# Universal_2022_06.net
KiCad netlist of a schematic drawn in EAGLE
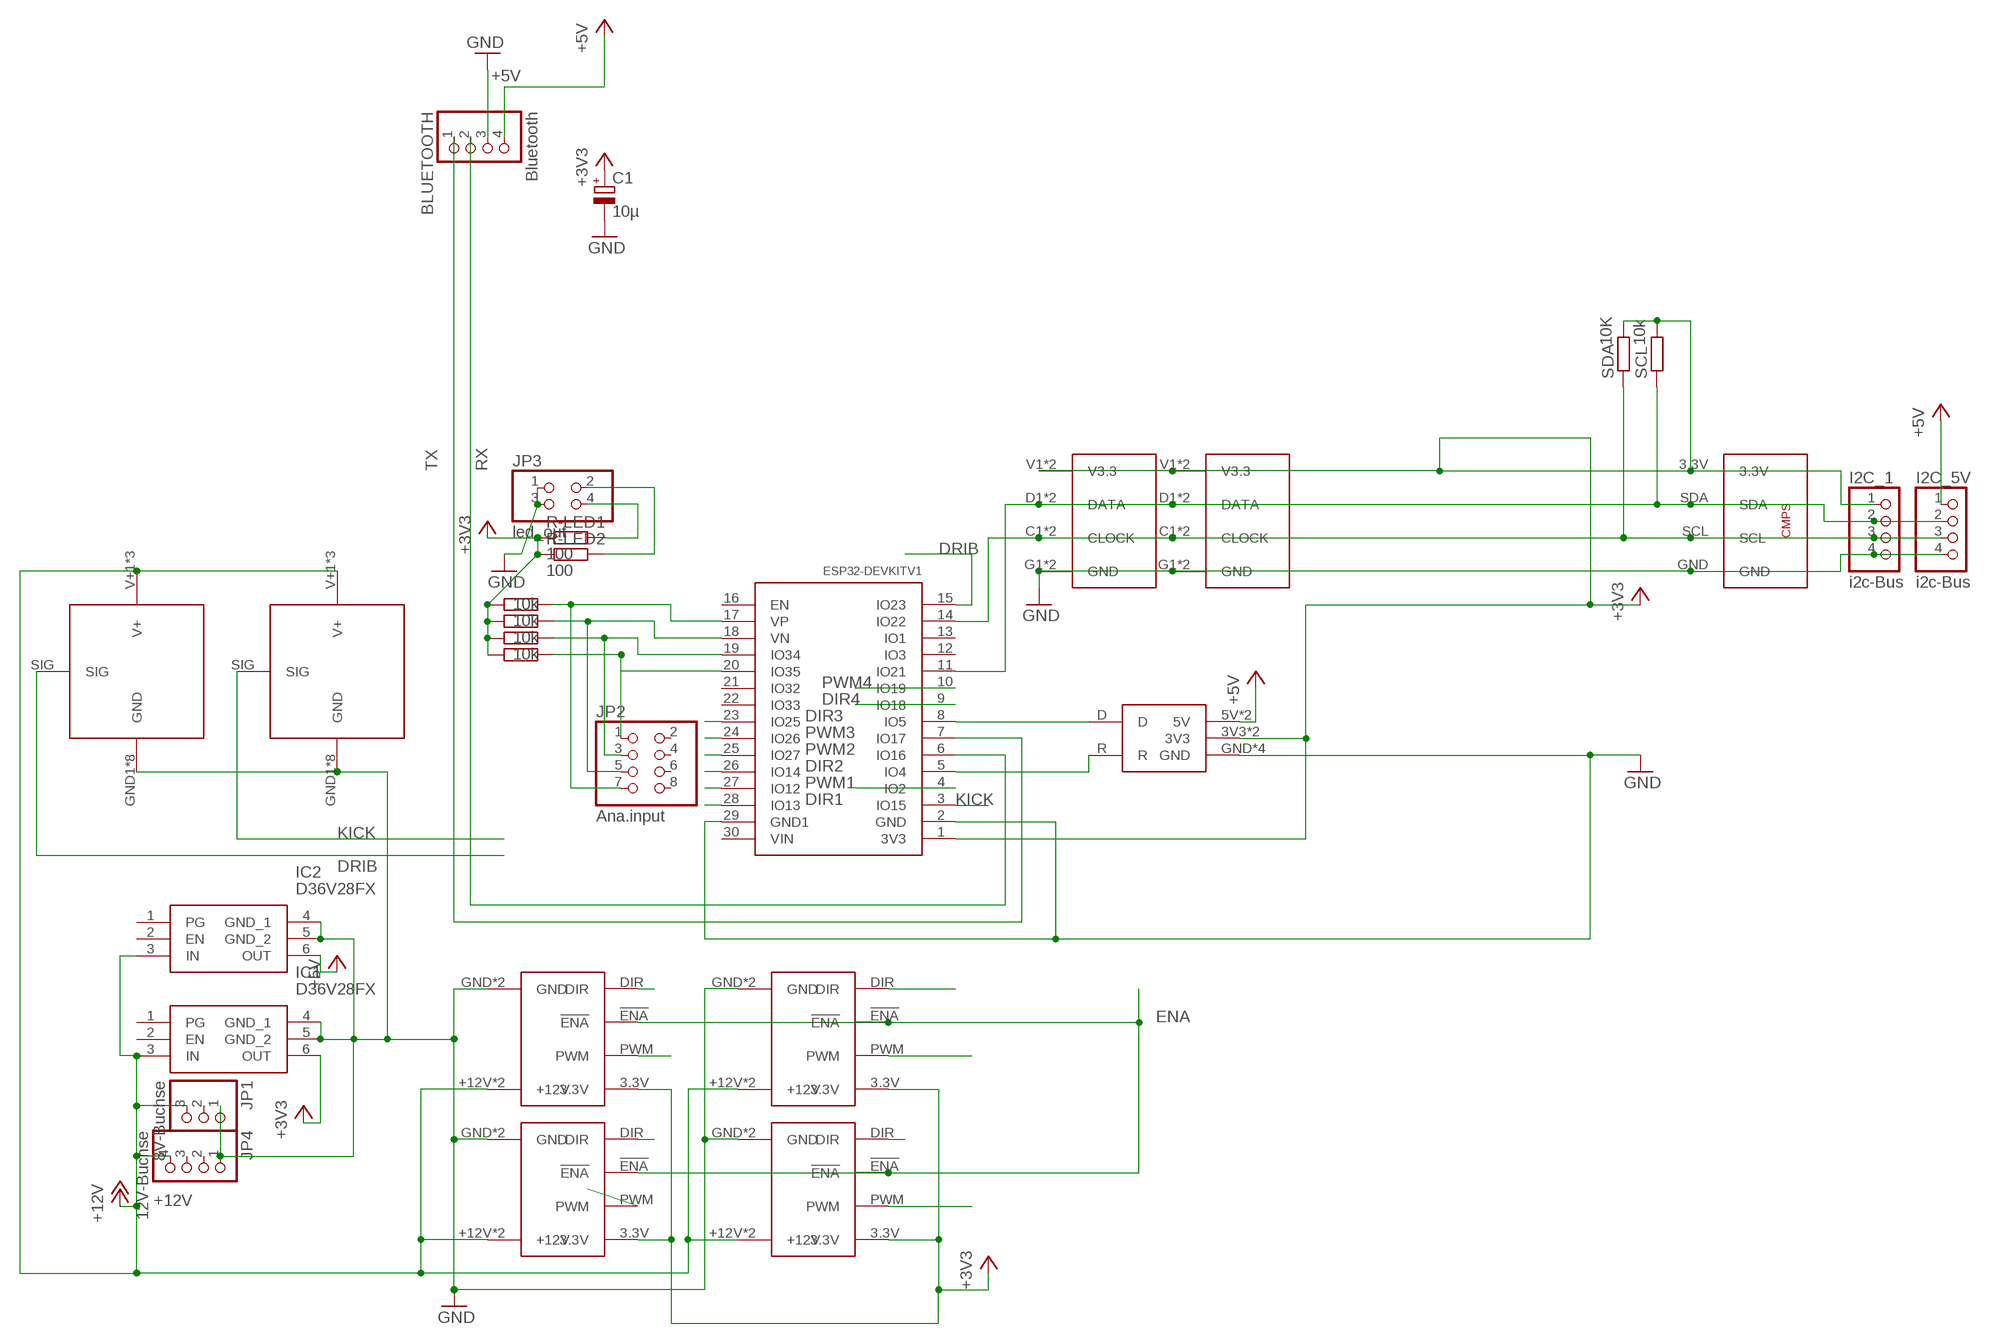
[diagram p0: schematic, sheet 1]

(export (version "E")
  (design (tool "Eeschema 10.0.6"))
  (components
    (comp (ref "BLUETOOTH")
      (value "Bluetooth")
      (footprint "eagle-import:1X04_90")
      (libsource (lib "eagle-import") (part "PINHD-1X4/90"))
    )
    (comp (ref "C1")
      (value "10µ")
      (footprint "eagle-import:E2,5-6E")
      (libsource (lib "eagle-import") (part "CPOL-EUE2,5-6E"))
    )
    (comp (ref "I2C_1")
      (value "i2c-Bus")
      (footprint "eagle-import:1X04")
      (libsource (lib "eagle-import") (part "PINHD-1X4"))
    )
    (comp (ref "I2C_5V")
      (value "i2c-Bus")
      (footprint "eagle-import:1X04")
      (libsource (lib "eagle-import") (part "PINHD-1X4"))
    )
    (comp (ref "IC1")
      (value "D36V28FX")
      (footprint "eagle-import:D36V28FX")
      (libsource (lib "eagle-import") (part "D36V28FX"))
    )
    (comp (ref "IC2")
      (value "D36V28FX")
      (footprint "eagle-import:D36V28FX")
      (libsource (lib "eagle-import") (part "D36V28FX"))
    )
    (comp (ref "JP1")
      (value "8V-Buchse")
      (footprint "eagle-import:1X03")
      (libsource (lib "eagle-import") (part "PINHD-1X3"))
    )
    (comp (ref "JP2")
      (value "Ana.input")
      (footprint "eagle-import:2X04")
      (libsource (lib "eagle-import") (part "PINHD-2X4"))
    )
    (comp (ref "JP3")
      (value "led_out")
      (footprint "eagle-import:2X02")
      (libsource (lib "eagle-import") (part "PINHD-2X2"))
    )
    (comp (ref "JP4")
      (value "12V-Buchse")
      (footprint "eagle-import:1X04")
      (libsource (lib "eagle-import") (part "PINHD-1X4"))
    )
    (comp (ref "R-LED1")
      (value "100")
      (footprint "eagle-import:0207_10")
      (libsource (lib "eagle-import") (part "R-EU_0207/10"))
    )
    (comp (ref "R-LED2")
      (value "100")
      (footprint "eagle-import:0207_10")
      (libsource (lib "eagle-import") (part "R-EU_0207/10"))
    )
    (comp (ref "R_AD14")
      (value "10k")
      (footprint "eagle-import:0207_10")
      (libsource (lib "eagle-import") (part "R-EU_0207/10"))
    )
    (comp (ref "R_AD25")
      (value "10k")
      (footprint "eagle-import:0207_10")
      (libsource (lib "eagle-import") (part "R-EU_0207/10"))
    )
    (comp (ref "R_AD26")
      (value "10k")
      (footprint "eagle-import:0207_10")
      (libsource (lib "eagle-import") (part "R-EU_0207/10"))
    )
    (comp (ref "R_AD27")
      (value "10k")
      (footprint "eagle-import:0207_10")
      (libsource (lib "eagle-import") (part "R-EU_0207/10"))
    )
    (comp (ref "SCL")
      (value "10k")
      (footprint "eagle-import:0207_10")
      (libsource (lib "eagle-import") (part "R-EU_0207/10"))
    )
    (comp (ref "SDA")
      (value "10K")
      (footprint "eagle-import:0207_10")
      (libsource (lib "eagle-import") (part "R-EU_0207/10"))
    )
    (comp (ref "U$1")
      (value "TASTER_LED")
      (footprint "eagle-import:TASTER_LED")
      (libsource (lib "eagle-import") (part "TASTER_LED"))
    )
    (comp (ref "U$3")
      (value "TASTER_LED")
      (footprint "eagle-import:TASTER_LED")
      (libsource (lib "eagle-import") (part "TASTER_LED"))
    )
    (comp (ref "U$5")
      (value "CANBUS")
      (footprint "eagle-import:CANBUS")
      (libsource (lib "eagle-import") (part "CANBUS"))
    )
    (comp (ref "U$7")
      (value "KICKER")
      (footprint "eagle-import:KICKER")
      (libsource (lib "eagle-import") (part "KICKER"))
    )
    (comp (ref "U$8")
      (value "CMPS")
      (footprint "eagle-import:CMPS")
      (libsource (lib "eagle-import") (part "CMPS"))
    )
    (comp (ref "U$11")
      (value "IFX9201BREAKOUT")
      (footprint "eagle-import:IFX9201BREAKOUT")
      (libsource (lib "eagle-import") (part "IFX9201BREAKOUT"))
    )
    (comp (ref "U$13")
      (value "ESP32DEVKITV1")
      (footprint "eagle-import:ESP32-DEVKITV1")
      (libsource (lib "eagle-import") (part "ESP32DEVKITV1"))
    )
    (comp (ref "U$14")
      (value "IFX9201BREAKOUT")
      (footprint "eagle-import:IFX9201BREAKOUT")
      (libsource (lib "eagle-import") (part "IFX9201BREAKOUT"))
    )
    (comp (ref "U$15")
      (value "IFX9201BREAKOUT")
      (footprint "eagle-import:IFX9201BREAKOUT")
      (libsource (lib "eagle-import") (part "IFX9201BREAKOUT"))
    )
    (comp (ref "U$16")
      (value "IFX9201BREAKOUT")
      (footprint "eagle-import:IFX9201BREAKOUT")
      (libsource (lib "eagle-import") (part "IFX9201BREAKOUT"))
    )
    (comp (ref "U$17")
      (value "KICKER")
      (footprint "eagle-import:KICKER")
      (libsource (lib "eagle-import") (part "KICKER"))
    )
  )
  (nets
    (net (code "1") (name "+3V3") (class "Default")
      (node (ref "C1") (pin "+") (pinfunction "+_+") (pintype "passive"))
      (node (ref "I2C_1") (pin "1") (pinfunction "1_1") (pintype "passive"))
      (node (ref "IC1") (pin "6") (pinfunction "OUT_6") (pintype "bidirectional"))
      (node (ref "R-LED1") (pin "1") (pinfunction "1_1") (pintype "passive"))
      (node (ref "R-LED2") (pin "1") (pinfunction "1_1") (pintype "passive"))
      (node (ref "R_AD14") (pin "1") (pinfunction "1_1") (pintype "passive"))
      (node (ref "R_AD25") (pin "1") (pinfunction "1_1") (pintype "passive"))
      (node (ref "R_AD26") (pin "1") (pinfunction "1_1") (pintype "passive"))
      (node (ref "R_AD27") (pin "1") (pinfunction "1_1") (pintype "passive"))
      (node (ref "SCL") (pin "2") (pinfunction "2_2") (pintype "passive"))
      (node (ref "SDA") (pin "2") (pinfunction "2_2") (pintype "passive"))
      (node (ref "U$1") (pin "V1") (pinfunction "V3.3_V1") (pintype "bidirectional"))
      (node (ref "U$1") (pin "V2") (pinfunction "V3.3_V2") (pintype "bidirectional"))
      (node (ref "U$11") (pin "3.3V") (pinfunction "3.3V_3.3V") (pintype "bidirectional"))
      (node (ref "U$13") (pin "1") (pinfunction "3V3_1") (pintype "bidirectional"))
      (node (ref "U$14") (pin "3.3V") (pinfunction "3.3V_3.3V") (pintype "bidirectional"))
      (node (ref "U$15") (pin "3.3V") (pinfunction "3.3V_3.3V") (pintype "bidirectional"))
      (node (ref "U$16") (pin "3.3V") (pinfunction "3.3V_3.3V") (pintype "bidirectional"))
      (node (ref "U$3") (pin "V1") (pinfunction "V3.3_V1") (pintype "bidirectional"))
      (node (ref "U$3") (pin "V2") (pinfunction "V3.3_V2") (pintype "bidirectional"))
      (node (ref "U$5") (pin "3V3") (pinfunction "3V3_3V3") (pintype "bidirectional"))
      (node (ref "U$5") (pin "3V3_1") (pinfunction "3V3_3V3_1") (pintype "bidirectional"))
      (node (ref "U$8") (pin "3.3V") (pinfunction "3.3V_3.3V") (pintype "bidirectional"))
    )
    (net (code "2") (name "+5V") (class "Default")
      (node (ref "BLUETOOTH") (pin "4") (pinfunction "4_4") (pintype "passive"))
      (node (ref "I2C_5V") (pin "1") (pinfunction "1_1") (pintype "passive"))
      (node (ref "IC2") (pin "6") (pinfunction "OUT_6") (pintype "bidirectional"))
      (node (ref "U$5") (pin "5V") (pinfunction "5V_5V") (pintype "bidirectional"))
      (node (ref "U$5") (pin "5V_1") (pinfunction "5V_5V_1") (pintype "bidirectional"))
    )
    (net (code "3") (name "+12V") (class "Default")
      (node (ref "IC1") (pin "3") (pinfunction "IN_3") (pintype "bidirectional"))
      (node (ref "IC2") (pin "3") (pinfunction "IN_3") (pintype "bidirectional"))
      (node (ref "JP1") (pin "3") (pinfunction "3_3") (pintype "passive"))
      (node (ref "JP4") (pin "4") (pinfunction "4_4") (pintype "passive"))
      (node (ref "U$11") (pin "+12V") (pinfunction "+12V_+12V") (pintype "bidirectional"))
      (node (ref "U$11") (pin "+12V2") (pinfunction "+12V_+12V2") (pintype "bidirectional"))
      (node (ref "U$14") (pin "+12V") (pinfunction "+12V_+12V") (pintype "bidirectional"))
      (node (ref "U$14") (pin "+12V2") (pinfunction "+12V_+12V2") (pintype "bidirectional"))
      (node (ref "U$15") (pin "+12V") (pinfunction "+12V_+12V") (pintype "bidirectional"))
      (node (ref "U$15") (pin "+12V2") (pinfunction "+12V_+12V2") (pintype "bidirectional"))
      (node (ref "U$16") (pin "+12V") (pinfunction "+12V_+12V") (pintype "bidirectional"))
      (node (ref "U$16") (pin "+12V2") (pinfunction "+12V_+12V2") (pintype "bidirectional"))
      (node (ref "U$17") (pin "V+1") (pinfunction "V+_V+1") (pintype "bidirectional"))
      (node (ref "U$17") (pin "V+2") (pinfunction "V+_V+2") (pintype "bidirectional"))
      (node (ref "U$17") (pin "V+3") (pinfunction "V+_V+3") (pintype "bidirectional"))
      (node (ref "U$7") (pin "V+1") (pinfunction "V+_V+1") (pintype "bidirectional"))
      (node (ref "U$7") (pin "V+2") (pinfunction "V+_V+2") (pintype "bidirectional"))
      (node (ref "U$7") (pin "V+3") (pinfunction "V+_V+3") (pintype "bidirectional"))
    )
    (net (code "4") (name "/DIR1") (class "Default")
      (node (ref "U$13") (pin "28") (pinfunction "IO13_28") (pintype "bidirectional"))
      (node (ref "U$16") (pin "DIR") (pinfunction "DIR_DIR") (pintype "bidirectional"))
    )
    (net (code "5") (name "/DIR2") (class "Default")
      (node (ref "U$13") (pin "26") (pinfunction "IO14_26") (pintype "bidirectional"))
      (node (ref "U$15") (pin "DIR") (pinfunction "DIR_DIR") (pintype "bidirectional"))
    )
    (net (code "6") (name "/DIR3") (class "Default")
      (node (ref "U$11") (pin "DIR") (pinfunction "DIR_DIR") (pintype "bidirectional"))
      (node (ref "U$13") (pin "23") (pinfunction "IO25_23") (pintype "bidirectional"))
    )
    (net (code "7") (name "/DIR4") (class "Default")
      (node (ref "U$13") (pin "9") (pinfunction "IO18_9") (pintype "bidirectional"))
      (node (ref "U$14") (pin "DIR") (pinfunction "DIR_DIR") (pintype "bidirectional"))
    )
    (net (code "8") (name "/DRIB") (class "Default")
      (node (ref "U$13") (pin "15") (pinfunction "IO23_15") (pintype "bidirectional"))
      (node (ref "U$7") (pin "SIG") (pinfunction "SIG_SIG") (pintype "bidirectional"))
    )
    (net (code "9") (name "/ENA") (class "Default")
      (node (ref "U$11") (pin "!ENA") (pinfunction "~{ENA}_!ENA") (pintype "bidirectional"))
      (node (ref "U$13") (pin "4") (pinfunction "IO2_4") (pintype "bidirectional"))
      (node (ref "U$14") (pin "!ENA") (pinfunction "~{ENA}_!ENA") (pintype "bidirectional"))
      (node (ref "U$15") (pin "!ENA") (pinfunction "~{ENA}_!ENA") (pintype "bidirectional"))
      (node (ref "U$16") (pin "!ENA") (pinfunction "~{ENA}_!ENA") (pintype "bidirectional"))
    )
    (net (code "10") (name "/KICK") (class "Default")
      (node (ref "U$13") (pin "3") (pinfunction "IO15_3") (pintype "bidirectional"))
      (node (ref "U$17") (pin "SIG") (pinfunction "SIG_SIG") (pintype "bidirectional"))
    )
    (net (code "11") (name "/PWM1") (class "Default")
      (node (ref "U$13") (pin "27") (pinfunction "IO12_27") (pintype "bidirectional"))
      (node (ref "U$16") (pin "PWM") (pinfunction "PWM_PWM") (pintype "bidirectional"))
    )
    (net (code "12") (name "/PWM2") (class "Default")
      (node (ref "U$13") (pin "25") (pinfunction "IO27_25") (pintype "bidirectional"))
      (node (ref "U$15") (pin "PWM") (pinfunction "PWM_PWM") (pintype "bidirectional"))
    )
    (net (code "13") (name "/PWM3") (class "Default")
      (node (ref "U$11") (pin "PWM") (pinfunction "PWM_PWM") (pintype "bidirectional"))
      (node (ref "U$13") (pin "24") (pinfunction "IO26_24") (pintype "bidirectional"))
    )
    (net (code "14") (name "/PWM4") (class "Default")
      (node (ref "U$13") (pin "10") (pinfunction "IO19_10") (pintype "bidirectional"))
      (node (ref "U$14") (pin "PWM") (pinfunction "PWM_PWM") (pintype "bidirectional"))
    )
    (net (code "15") (name "/RX") (class "Default")
      (node (ref "BLUETOOTH") (pin "2") (pinfunction "2_2") (pintype "passive"))
      (node (ref "U$13") (pin "6") (pinfunction "IO16_6") (pintype "bidirectional"))
    )
    (net (code "16") (name "/TX") (class "Default")
      (node (ref "BLUETOOTH") (pin "1") (pinfunction "1_1") (pintype "passive"))
      (node (ref "U$13") (pin "7") (pinfunction "IO17_7") (pintype "bidirectional"))
    )
    (net (code "17") (name "GND") (class "Default")
      (node (ref "BLUETOOTH") (pin "3") (pinfunction "3_3") (pintype "passive"))
      (node (ref "C1") (pin "-") (pinfunction "-_-") (pintype "passive"))
      (node (ref "I2C_1") (pin "4") (pinfunction "4_4") (pintype "passive"))
      (node (ref "I2C_5V") (pin "4") (pinfunction "4_4") (pintype "passive"))
      (node (ref "IC1") (pin "4") (pinfunction "GND_1_4") (pintype "bidirectional"))
      (node (ref "IC1") (pin "5") (pinfunction "GND_2_5") (pintype "bidirectional"))
      (node (ref "IC2") (pin "4") (pinfunction "GND_1_4") (pintype "bidirectional"))
      (node (ref "IC2") (pin "5") (pinfunction "GND_2_5") (pintype "bidirectional"))
      (node (ref "JP1") (pin "1") (pinfunction "1_1") (pintype "passive"))
      (node (ref "JP3") (pin "1") (pinfunction "1_1") (pintype "passive"))
      (node (ref "JP3") (pin "3") (pinfunction "3_3") (pintype "passive"))
      (node (ref "JP4") (pin "1") (pinfunction "1_1") (pintype "passive"))
      (node (ref "U$1") (pin "G1") (pinfunction "GND_G1") (pintype "bidirectional"))
      (node (ref "U$1") (pin "G2") (pinfunction "GND_G2") (pintype "bidirectional"))
      (node (ref "U$11") (pin "GND") (pinfunction "GND_GND") (pintype "bidirectional"))
      (node (ref "U$11") (pin "GND2") (pinfunction "GND_GND2") (pintype "bidirectional"))
      (node (ref "U$13") (pin "2") (pinfunction "GND_2") (pintype "bidirectional"))
      (node (ref "U$13") (pin "29") (pinfunction "GND1_29") (pintype "bidirectional"))
      (node (ref "U$14") (pin "GND") (pinfunction "GND_GND") (pintype "bidirectional"))
      (node (ref "U$14") (pin "GND2") (pinfunction "GND_GND2") (pintype "bidirectional"))
      (node (ref "U$15") (pin "GND") (pinfunction "GND_GND") (pintype "bidirectional"))
      (node (ref "U$15") (pin "GND2") (pinfunction "GND_GND2") (pintype "bidirectional"))
      (node (ref "U$16") (pin "GND") (pinfunction "GND_GND") (pintype "bidirectional"))
      (node (ref "U$16") (pin "GND2") (pinfunction "GND_GND2") (pintype "bidirectional"))
      (node (ref "U$17") (pin "GND1") (pinfunction "GND_GND1") (pintype "bidirectional"))
      (node (ref "U$17") (pin "GND2") (pinfunction "GND_GND2") (pintype "bidirectional"))
      (node (ref "U$17") (pin "GND3") (pinfunction "GND_GND3") (pintype "bidirectional"))
      (node (ref "U$17") (pin "GND4") (pinfunction "GND_GND4") (pintype "bidirectional"))
      (node (ref "U$17") (pin "GND5") (pinfunction "GND_GND5") (pintype "bidirectional"))
      (node (ref "U$17") (pin "GND6") (pinfunction "GND_GND6") (pintype "bidirectional"))
      (node (ref "U$17") (pin "GND7") (pinfunction "GND_GND7") (pintype "bidirectional"))
      (node (ref "U$17") (pin "GND8") (pinfunction "GND_GND8") (pintype "bidirectional"))
      (node (ref "U$3") (pin "G1") (pinfunction "GND_G1") (pintype "bidirectional"))
      (node (ref "U$3") (pin "G2") (pinfunction "GND_G2") (pintype "bidirectional"))
      (node (ref "U$5") (pin "GND") (pinfunction "GND_GND") (pintype "bidirectional"))
      (node (ref "U$5") (pin "GND_1") (pinfunction "GND_GND_1") (pintype "bidirectional"))
      (node (ref "U$5") (pin "GND_2") (pinfunction "GND_GND_2") (pintype "bidirectional"))
      (node (ref "U$5") (pin "GND_3") (pinfunction "GND_GND_3") (pintype "bidirectional"))
      (node (ref "U$7") (pin "GND1") (pinfunction "GND_GND1") (pintype "bidirectional"))
      (node (ref "U$7") (pin "GND2") (pinfunction "GND_GND2") (pintype "bidirectional"))
      (node (ref "U$7") (pin "GND3") (pinfunction "GND_GND3") (pintype "bidirectional"))
      (node (ref "U$7") (pin "GND4") (pinfunction "GND_GND4") (pintype "bidirectional"))
      (node (ref "U$7") (pin "GND5") (pinfunction "GND_GND5") (pintype "bidirectional"))
      (node (ref "U$7") (pin "GND6") (pinfunction "GND_GND6") (pintype "bidirectional"))
      (node (ref "U$7") (pin "GND7") (pinfunction "GND_GND7") (pintype "bidirectional"))
      (node (ref "U$7") (pin "GND8") (pinfunction "GND_GND8") (pintype "bidirectional"))
      (node (ref "U$8") (pin "GND") (pinfunction "GND_GND") (pintype "bidirectional"))
    )
    (net (code "18") (name "Net-(JP3-Pad2)") (class "Default")
      (node (ref "JP3") (pin "2") (pinfunction "2_2") (pintype "passive"))
      (node (ref "R-LED2") (pin "2") (pinfunction "2_2") (pintype "passive"))
    )
    (net (code "19") (name "Net-(JP3-Pad4)") (class "Default")
      (node (ref "JP3") (pin "4") (pinfunction "4_4") (pintype "passive"))
      (node (ref "R-LED1") (pin "2") (pinfunction "2_2") (pintype "passive"))
    )
    (net (code "20") (name "Net-(U$13-IO4)") (class "Default")
      (node (ref "U$13") (pin "5") (pinfunction "IO4_5") (pintype "bidirectional"))
      (node (ref "U$5") (pin "R") (pinfunction "R_R") (pintype "bidirectional"))
    )
    (net (code "21") (name "Net-(U$13-IO5)") (class "Default")
      (node (ref "U$13") (pin "8") (pinfunction "IO5_8") (pintype "bidirectional"))
      (node (ref "U$5") (pin "D") (pinfunction "D_D") (pintype "bidirectional"))
    )
    (net (code "22") (name "Net-(U$13-IO21)") (class "Default")
      (node (ref "I2C_1") (pin "2") (pinfunction "2_2") (pintype "passive"))
      (node (ref "I2C_5V") (pin "2") (pinfunction "2_2") (pintype "passive"))
      (node (ref "SCL") (pin "1") (pinfunction "1_1") (pintype "passive"))
      (node (ref "U$1") (pin "D1") (pinfunction "DATA_D1") (pintype "bidirectional"))
      (node (ref "U$1") (pin "D2") (pinfunction "DATA_D2") (pintype "bidirectional"))
      (node (ref "U$13") (pin "11") (pinfunction "IO21_11") (pintype "bidirectional"))
      (node (ref "U$3") (pin "D1") (pinfunction "DATA_D1") (pintype "bidirectional"))
      (node (ref "U$3") (pin "D2") (pinfunction "DATA_D2") (pintype "bidirectional"))
      (node (ref "U$8") (pin "SDA") (pinfunction "SDA_SDA") (pintype "bidirectional"))
    )
    (net (code "23") (name "Net-(U$13-IO22)") (class "Default")
      (node (ref "I2C_1") (pin "3") (pinfunction "3_3") (pintype "passive"))
      (node (ref "I2C_5V") (pin "3") (pinfunction "3_3") (pintype "passive"))
      (node (ref "SDA") (pin "1") (pinfunction "1_1") (pintype "passive"))
      (node (ref "U$1") (pin "C1") (pinfunction "CLOCK_C1") (pintype "bidirectional"))
      (node (ref "U$1") (pin "C2") (pinfunction "CLOCK_C2") (pintype "bidirectional"))
      (node (ref "U$13") (pin "14") (pinfunction "IO22_14") (pintype "bidirectional"))
      (node (ref "U$3") (pin "C1") (pinfunction "CLOCK_C1") (pintype "bidirectional"))
      (node (ref "U$3") (pin "C2") (pinfunction "CLOCK_C2") (pintype "bidirectional"))
      (node (ref "U$8") (pin "SCL") (pinfunction "SCL_SCL") (pintype "bidirectional"))
    )
    (net (code "24") (name "Net-(U$13-IO34)") (class "Default")
      (node (ref "JP2") (pin "3") (pinfunction "3_3") (pintype "passive"))
      (node (ref "R_AD27") (pin "2") (pinfunction "2_2") (pintype "passive"))
      (node (ref "U$13") (pin "19") (pinfunction "IO34_19") (pintype "bidirectional"))
    )
    (net (code "25") (name "Net-(U$13-IO35)") (class "Default")
      (node (ref "JP2") (pin "1") (pinfunction "1_1") (pintype "passive"))
      (node (ref "R_AD14") (pin "2") (pinfunction "2_2") (pintype "passive"))
      (node (ref "U$13") (pin "20") (pinfunction "IO35_20") (pintype "bidirectional"))
    )
    (net (code "26") (name "Net-(U$13-VN)") (class "Default")
      (node (ref "JP2") (pin "5") (pinfunction "5_5") (pintype "passive"))
      (node (ref "R_AD26") (pin "2") (pinfunction "2_2") (pintype "passive"))
      (node (ref "U$13") (pin "18") (pinfunction "VN_18") (pintype "bidirectional"))
    )
    (net (code "27") (name "Net-(U$13-VP)") (class "Default")
      (node (ref "JP2") (pin "7") (pinfunction "7_7") (pintype "passive"))
      (node (ref "R_AD25") (pin "2") (pinfunction "2_2") (pintype "passive"))
      (node (ref "U$13") (pin "17") (pinfunction "VP_17") (pintype "bidirectional"))
    )
    (net (code "28") (name "unconnected-(IC1-EN-Pad2)") (class "Default")
      (node (ref "IC1") (pin "2") (pinfunction "EN_2") (pintype "bidirectional"))
    )
    (net (code "29") (name "unconnected-(IC1-PG-Pad1)") (class "Default")
      (node (ref "IC1") (pin "1") (pinfunction "PG_1") (pintype "bidirectional"))
    )
    (net (code "30") (name "unconnected-(IC2-EN-Pad2)") (class "Default")
      (node (ref "IC2") (pin "2") (pinfunction "EN_2") (pintype "bidirectional"))
    )
    (net (code "31") (name "unconnected-(IC2-PG-Pad1)") (class "Default")
      (node (ref "IC2") (pin "1") (pinfunction "PG_1") (pintype "bidirectional"))
    )
    (net (code "32") (name "unconnected-(JP1-Pad2)") (class "Default")
      (node (ref "JP1") (pin "2") (pinfunction "2_2") (pintype "passive"))
    )
    (net (code "33") (name "unconnected-(JP2-Pad2)") (class "Default")
      (node (ref "JP2") (pin "2") (pinfunction "2_2") (pintype "passive"))
    )
    (net (code "34") (name "unconnected-(JP2-Pad4)") (class "Default")
      (node (ref "JP2") (pin "4") (pinfunction "4_4") (pintype "passive"))
    )
    (net (code "35") (name "unconnected-(JP2-Pad6)") (class "Default")
      (node (ref "JP2") (pin "6") (pinfunction "6_6") (pintype "passive"))
    )
    (net (code "36") (name "unconnected-(JP2-Pad8)") (class "Default")
      (node (ref "JP2") (pin "8") (pinfunction "8_8") (pintype "passive"))
    )
    (net (code "37") (name "unconnected-(JP4-Pad2)") (class "Default")
      (node (ref "JP4") (pin "2") (pinfunction "2_2") (pintype "passive"))
    )
    (net (code "38") (name "unconnected-(JP4-Pad3)") (class "Default")
      (node (ref "JP4") (pin "3") (pinfunction "3_3") (pintype "passive"))
    )
    (net (code "39") (name "unconnected-(U$13-EN-Pad16)") (class "Default")
      (node (ref "U$13") (pin "16") (pinfunction "EN_16") (pintype "bidirectional"))
    )
    (net (code "40") (name "unconnected-(U$13-IO1-Pad13)") (class "Default")
      (node (ref "U$13") (pin "13") (pinfunction "IO1_13") (pintype "bidirectional"))
    )
    (net (code "41") (name "unconnected-(U$13-IO3-Pad12)") (class "Default")
      (node (ref "U$13") (pin "12") (pinfunction "IO3_12") (pintype "bidirectional"))
    )
    (net (code "42") (name "unconnected-(U$13-IO32-Pad21)") (class "Default")
      (node (ref "U$13") (pin "21") (pinfunction "IO32_21") (pintype "bidirectional"))
    )
    (net (code "43") (name "unconnected-(U$13-IO33-Pad22)") (class "Default")
      (node (ref "U$13") (pin "22") (pinfunction "IO33_22") (pintype "bidirectional"))
    )
    (net (code "44") (name "unconnected-(U$13-VIN-Pad30)") (class "Default")
      (node (ref "U$13") (pin "30") (pinfunction "VIN_30") (pintype "bidirectional"))
    )
  )
)
